# Super-Regenerative-VHF-2Transistor-RickA.net
KiCad netlist of a schematic drawn in EAGLE
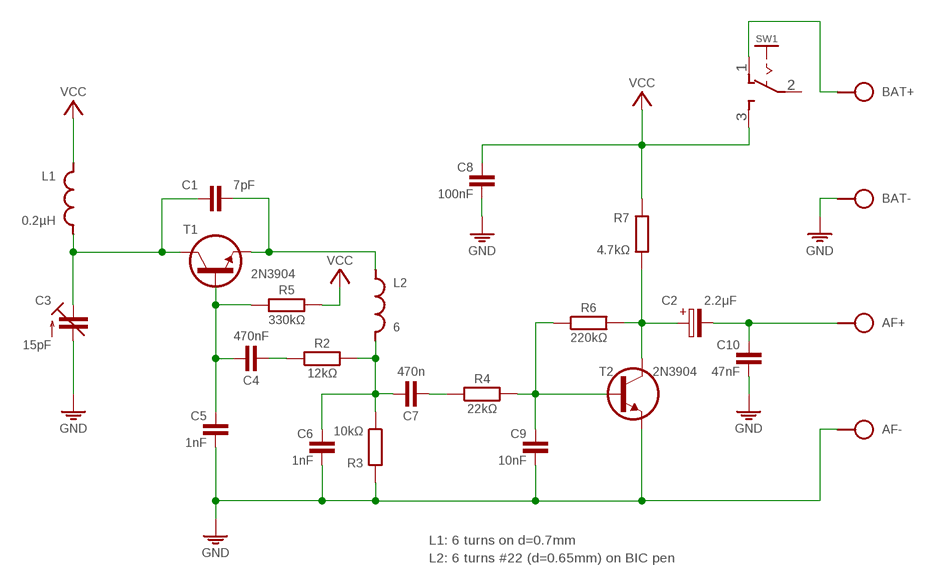
[diagram p0: schematic, sheet 1]

(export (version "E")
  (design (tool "Eeschema 10.0.6"))
  (components
    (comp (ref "AF+")
      (value "SPAD")
      (footprint "eagle-import:SPAD")
      (libsource (lib "eagle-import") (part "SPAD"))
    )
    (comp (ref "AF-")
      (value "SPAD")
      (footprint "eagle-import:SPAD")
      (libsource (lib "eagle-import") (part "SPAD"))
    )
    (comp (ref "BAT+")
      (value "SPAD")
      (footprint "eagle-import:SPAD")
      (libsource (lib "eagle-import") (part "SPAD"))
    )
    (comp (ref "BAT-")
      (value "SPAD")
      (footprint "eagle-import:SPAD")
      (libsource (lib "eagle-import") (part "SPAD"))
    )
    (comp (ref "C1")
      (value "7pF")
      (footprint "eagle-import:C025-020X036")
      (libsource (lib "eagle-import") (part "C025-020X036"))
    )
    (comp (ref "C2")
      (value "2.2μF")
      (footprint "eagle-import:E2,5-3")
      (libsource (lib "eagle-import") (part "CPOLE2,5-3"))
    )
    (comp (ref "C3")
      (value "15pF")
      (footprint "eagle-import:TRIM-2222-808")
      (libsource (lib "eagle-import") (part "C-TR-PH201272222-808-2PINB"))
    )
    (comp (ref "C4")
      (value "470nF")
      (footprint "eagle-import:C050-024X044_V")
      (libsource (lib "eagle-import") (part "C-H050-024X044/V"))
    )
    (comp (ref "C5")
      (value "1nF")
      (footprint "eagle-import:C025-020X036")
      (libsource (lib "eagle-import") (part "C025-020X036"))
    )
    (comp (ref "C6")
      (value "1nF")
      (footprint "eagle-import:C025-020X036")
      (libsource (lib "eagle-import") (part "C025-020X036"))
    )
    (comp (ref "C7")
      (value "470n")
      (footprint "eagle-import:C075-020X044")
      (libsource (lib "eagle-import") (part "C-H075-020X044"))
    )
    (comp (ref "C8")
      (value "100nF")
      (footprint "eagle-import:C050-020X036")
      (libsource (lib "eagle-import") (part "C050-020X036"))
    )
    (comp (ref "C9")
      (value "10nF")
      (footprint "eagle-import:C050-025X075")
      (libsource (lib "eagle-import") (part "C050-025X075"))
    )
    (comp (ref "C10")
      (value "47nF")
      (footprint "eagle-import:C050-025X075")
      (libsource (lib "eagle-import") (part "C050-025X075"))
    )
    (comp (ref "L1")
      (value "0.2µH")
      (footprint "eagle-import:L-04_8V")
      (libsource (lib "eagle-import") (part "L-SHORTL-04/8V"))
    )
    (comp (ref "L2")
      (value "6")
      (footprint "eagle-import:L-04_8V")
      (libsource (lib "eagle-import") (part "L-SHORTL-04/8V"))
    )
    (comp (ref "R2")
      (value "12kΩ")
      (footprint "eagle-import:0204_10")
      (libsource (lib "eagle-import") (part "R-H0204/10"))
    )
    (comp (ref "R3")
      (value "10kΩ")
      (footprint "eagle-import:0204_10")
      (libsource (lib "eagle-import") (part "R0204/10"))
    )
    (comp (ref "R4")
      (value "22kΩ")
      (footprint "eagle-import:0204_10")
      (libsource (lib "eagle-import") (part "R-H0204/10"))
    )
    (comp (ref "R5")
      (value "330kΩ")
      (footprint "eagle-import:0204_10")
      (libsource (lib "eagle-import") (part "R-H0204/10"))
    )
    (comp (ref "R6")
      (value "220kΩ")
      (footprint "eagle-import:0204_10")
      (libsource (lib "eagle-import") (part "R-H0204/10"))
    )
    (comp (ref "R7")
      (value "4.7kΩ")
      (footprint "eagle-import:0204_10")
      (libsource (lib "eagle-import") (part "R0204/10"))
    )
    (comp (ref "SW1")
      (value "SL-SW-1P-2T-H")
      (footprint "eagle-import:SLSW-1P2T-H")
      (libsource (lib "eagle-import") (part "SL-SW-1P-2T-H"))
    )
    (comp (ref "T1")
      (value "2N3904")
      (footprint "eagle-import:TO92")
      (libsource (lib "eagle-import") (part "2N3904"))
    )
    (comp (ref "T2")
      (value "2N3904")
      (footprint "eagle-import:TO92")
      (libsource (lib "eagle-import") (part "2N3904"))
    )
  )
  (nets
    (net (code "1") (name "GND") (class "Default")
      (node (ref "AF-") (pin "1") (pinfunction "P$1_1") (pintype "bidirectional"))
      (node (ref "BAT-") (pin "1") (pinfunction "P$1_1") (pintype "bidirectional"))
      (node (ref "C10") (pin "2") (pinfunction "2_2") (pintype "passive"))
      (node (ref "C3") (pin "2") (pinfunction "A_2") (pintype "passive"))
      (node (ref "C5") (pin "2") (pinfunction "2_2") (pintype "passive"))
      (node (ref "C6") (pin "2") (pinfunction "2_2") (pintype "passive"))
      (node (ref "C8") (pin "2") (pinfunction "2_2") (pintype "passive"))
      (node (ref "C9") (pin "2") (pinfunction "2_2") (pintype "passive"))
      (node (ref "R3") (pin "2") (pinfunction "2_2") (pintype "passive"))
      (node (ref "T2") (pin "1") (pinfunction "E_1") (pintype "passive"))
    )
    (net (code "2") (name "Net-(AF+-P$1)") (class "Default")
      (node (ref "AF+") (pin "1") (pinfunction "P$1_1") (pintype "bidirectional"))
      (node (ref "C10") (pin "1") (pinfunction "1_1") (pintype "passive"))
      (node (ref "C2") (pin "-") (pinfunction "-_-") (pintype "passive"))
    )
    (net (code "3") (name "Net-(BAT+-P$1)") (class "Default")
      (node (ref "BAT+") (pin "1") (pinfunction "P$1_1") (pintype "bidirectional"))
      (node (ref "SW1") (pin "1") (pinfunction "O_1") (pintype "passive"))
    )
    (net (code "4") (name "Net-(C3-E)") (class "Default")
      (node (ref "C1") (pin "2") (pinfunction "2_2") (pintype "passive"))
      (node (ref "C3") (pin "3") (pinfunction "E_3") (pintype "passive"))
      (node (ref "L1") (pin "1") (pinfunction "1_1") (pintype "passive"))
      (node (ref "T1") (pin "3") (pinfunction "C_3") (pintype "passive"))
    )
    (net (code "5") (name "Net-(C4-Pad1)") (class "Default")
      (node (ref "C4") (pin "1") (pinfunction "1_1") (pintype "passive"))
      (node (ref "R2") (pin "1") (pinfunction "1_1") (pintype "passive"))
    )
    (net (code "6") (name "Net-(C6-Pad1)") (class "Default")
      (node (ref "C6") (pin "1") (pinfunction "1_1") (pintype "passive"))
      (node (ref "C7") (pin "2") (pinfunction "2_2") (pintype "passive"))
      (node (ref "L2") (pin "1") (pinfunction "1_1") (pintype "passive"))
      (node (ref "R2") (pin "2") (pinfunction "2_2") (pintype "passive"))
      (node (ref "R3") (pin "1") (pinfunction "1_1") (pintype "passive"))
    )
    (net (code "7") (name "Net-(C7-Pad1)") (class "Default")
      (node (ref "C7") (pin "1") (pinfunction "1_1") (pintype "passive"))
      (node (ref "R4") (pin "1") (pinfunction "1_1") (pintype "passive"))
    )
    (net (code "8") (name "Net-(T1-B)") (class "Default")
      (node (ref "C4") (pin "2") (pinfunction "2_2") (pintype "passive"))
      (node (ref "C5") (pin "1") (pinfunction "1_1") (pintype "passive"))
      (node (ref "R5") (pin "2") (pinfunction "2_2") (pintype "passive"))
      (node (ref "T1") (pin "2") (pinfunction "B_2") (pintype "passive"))
    )
    (net (code "9") (name "Net-(T1-E)") (class "Default")
      (node (ref "C1") (pin "1") (pinfunction "1_1") (pintype "passive"))
      (node (ref "L2") (pin "2") (pinfunction "2_2") (pintype "passive"))
      (node (ref "T1") (pin "1") (pinfunction "E_1") (pintype "passive"))
    )
    (net (code "10") (name "Net-(T2-B)") (class "Default")
      (node (ref "C9") (pin "1") (pinfunction "1_1") (pintype "passive"))
      (node (ref "R4") (pin "2") (pinfunction "2_2") (pintype "passive"))
      (node (ref "R6") (pin "1") (pinfunction "1_1") (pintype "passive"))
      (node (ref "T2") (pin "2") (pinfunction "B_2") (pintype "passive"))
    )
    (net (code "11") (name "Net-(T2-C)") (class "Default")
      (node (ref "C2") (pin "+") (pinfunction "+_+") (pintype "passive"))
      (node (ref "R6") (pin "2") (pinfunction "2_2") (pintype "passive"))
      (node (ref "R7") (pin "1") (pinfunction "1_1") (pintype "passive"))
      (node (ref "T2") (pin "3") (pinfunction "C_3") (pintype "passive"))
    )
    (net (code "12") (name "VCC") (class "Default")
      (node (ref "C8") (pin "1") (pinfunction "1_1") (pintype "passive"))
      (node (ref "L1") (pin "2") (pinfunction "2_2") (pintype "passive"))
      (node (ref "R5") (pin "1") (pinfunction "1_1") (pintype "passive"))
      (node (ref "R7") (pin "2") (pinfunction "2_2") (pintype "passive"))
      (node (ref "SW1") (pin "3") (pinfunction "S_3") (pintype "passive"))
    )
    (net (code "13") (name "unconnected-(SW1-P-Pad2)") (class "Default")
      (node (ref "SW1") (pin "2") (pinfunction "P_2") (pintype "passive"))
    )
  )
)
